# Peripherals.net
KiCad netlist of a schematic drawn in Altium Designer
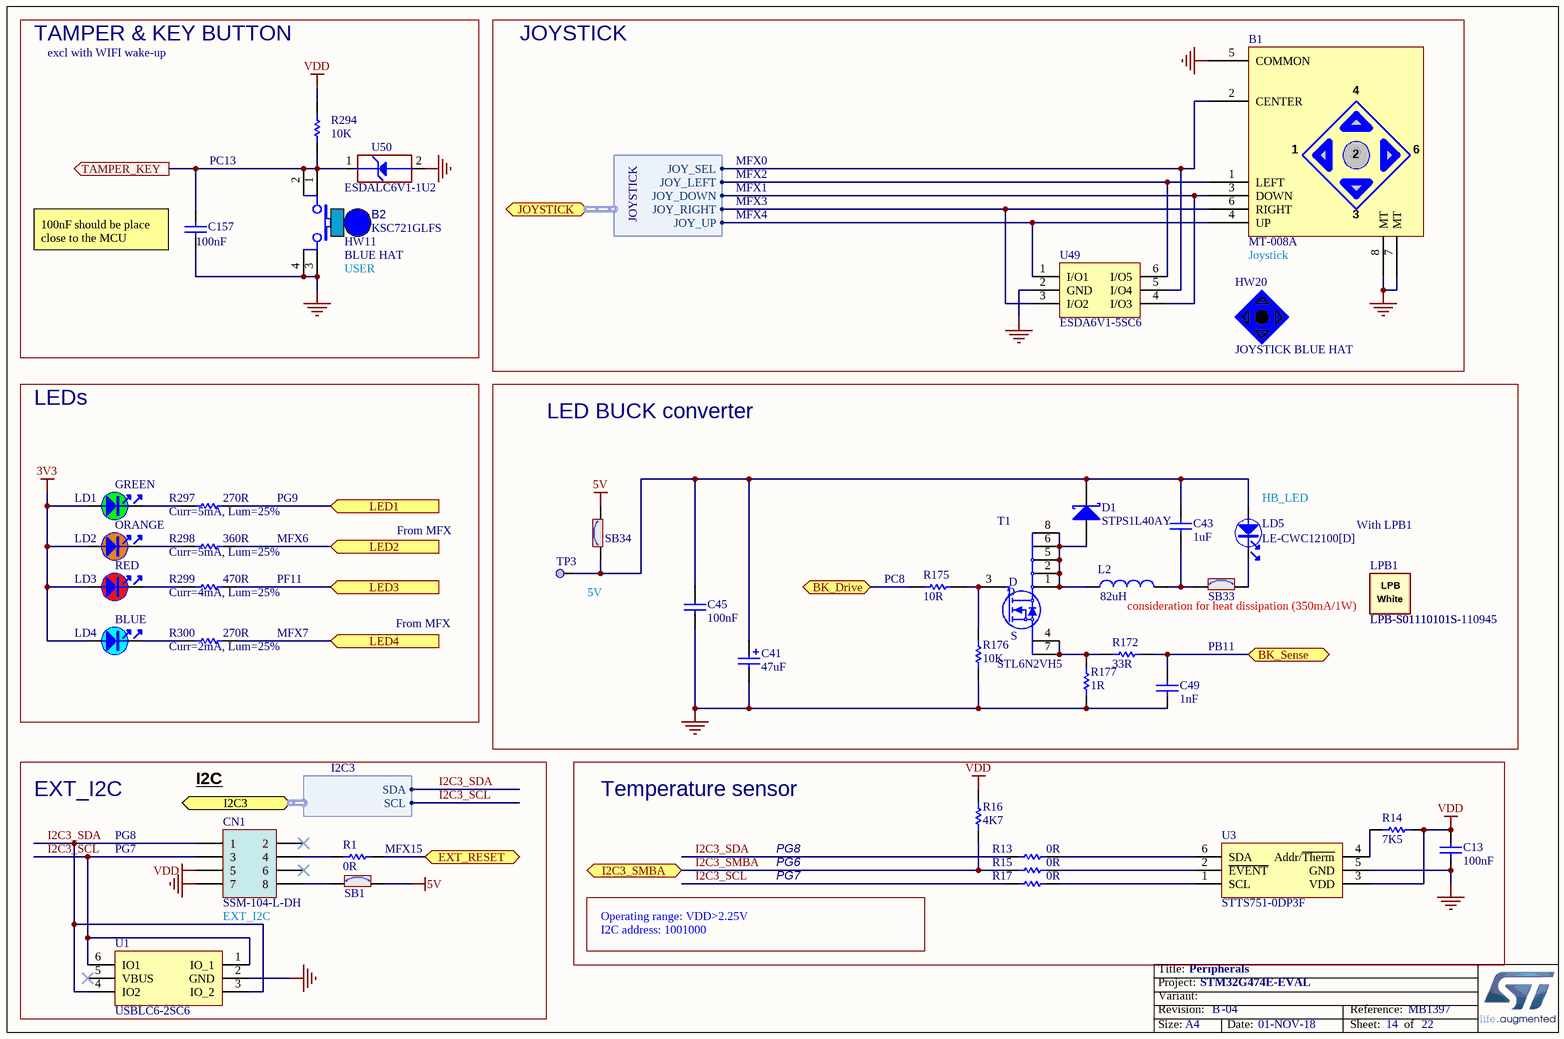
[diagram p0: Peripherals.SchDoc]

(export (version "E")
  (design (tool "Eeschema 10.0.6"))
  (components
    (comp (ref "B1")
      (value "MT-008A")
      (footprint "SWI_XIEJIA_MT-008A_6P")
      (description "Joystick, 4 dir, 1 OK")
      (fields
        (field (name "INTERNAL_PART_NUMBER") "MCD-00132")
        (field (name "MANUFACTURER") "XIEJIA Electronics")
        (field (name "PROVIDED_BY") "SUBCO")
      )
      (libsource (lib "MCD_PARTS_database") (part "Joystick MT-008A_M"))
    )
    (comp (ref "B2")
      (value "KSC721GLFS")
      (footprint "SWI_C&K_KSC721GLFS_BLUE")
      (description "Switch HW BLUE High4.3mm 2.25 Newtons")
      (fields
        (field (name "INTERNAL_PART_NUMBER") "MCD-00176")
        (field (name "MANUFACTURER") "C&K")
        (field (name "PROVIDED_BY") "SUBCO")
      )
      (libsource (lib "MCD_PARTS_database") (part "SW_BLUE_KSC721GLFS"))
    )
    (comp (ref "C13")
      (value "100nF")
      (footprint "C0603")
      (description "Capacitor, MLCC, 100nF, 16V, X7R, 10%, 0603, T=0,8mm")
      (fields
        (field (name "INTERNAL_PART_NUMBER") "MCD-00211")
        (field (name "MANUFACTURER_PART_NUMBER") "CC0603KRX7R7BB104")
        (field (name "PROVIDED_BY") "SUBCO")
      )
      (libsource (lib "MCD_PARTS_database") (part "Capacitor"))
    )
    (comp (ref "C41")
      (value "47uF")
      (footprint "CPOL_TAJ-C_2312_H2P6")
      (description "Capacitor, Tantalum, 47uF, 16V, 10%, TypeC")
      (fields
        (field (name "INTERNAL_PART_NUMBER") "MCD-00559")
        (field (name "MANUFACTURER_PART_NUMBER") "TAJC476K016RNJ")
        (field (name "PROVIDED_BY") "SUBCO")
      )
      (libsource (lib "MCD_PARTS_database") (part "Cap_POL_TANA"))
    )
    (comp (ref "C43")
      (value "1uF")
      (footprint "C0603")
      (description "Capacitor, MLCC, 1uF, 16V, X5R, 10%, 0603, T=0,8mm")
      (fields
        (field (name "INTERNAL_PART_NUMBER") "MCD-00010")
        (field (name "MANUFACTURER_PART_NUMBER") "CC0603KRX5R7BB105")
        (field (name "PROVIDED_BY") "SUBCO")
      )
      (libsource (lib "MCD_PARTS_database") (part "Capacitor"))
    )
    (comp (ref "C45")
      (value "100nF")
      (footprint "C0603")
      (description "Capacitor, MLCC, 100nF, 16V, X7R, 10%, 0603, T=0,8mm")
      (fields
        (field (name "INTERNAL_PART_NUMBER") "MCD-00211")
        (field (name "MANUFACTURER_PART_NUMBER") "CC0603KRX7R7BB104")
        (field (name "PROVIDED_BY") "SUBCO")
      )
      (libsource (lib "MCD_PARTS_database") (part "Capacitor"))
    )
    (comp (ref "C49")
      (value "1nF")
      (footprint "C0402")
      (description "Capacitor, MLCC, 1nF, 16V, X7R, 10%, 0402, T=0.5mm")
      (fields
        (field (name "INTERNAL_PART_NUMBER") "MCD-00198")
        (field (name "MANUFACTURER_PART_NUMBER") "CC0402KRX7R7BB102")
        (field (name "PROVIDED_BY") "SUBCO")
      )
      (libsource (lib "MCD_PARTS_database") (part "Capacitor"))
    )
    (comp (ref "C157")
      (value "100nF")
      (footprint "C0402")
      (description "Capacitor, MLCC, 100nF, 16V, X7R, 10%, 0402, T=0.5mm")
      (fields
        (field (name "INTERNAL_PART_NUMBER") "MCD-00006")
        (field (name "MANUFACTURER_PART_NUMBER") "CC0402KRX7R7BB104")
        (field (name "PROVIDED_BY") "SUBCO")
      )
      (libsource (lib "MCD_PARTS_database") (part "Capacitor"))
    )
    (comp (ref "CN1")
      (value "SSM-104-L-DH")
      (footprint "CON_SAMTEC_SSM-104-L-DH")
      (description "Socket, 4x2, 2.54mm, RA, SMT, Height 5.72mm")
      (fields
        (field (name "INTERNAL_PART_NUMBER") "MCD-00131")
        (field (name "MANUFACTURER") "SAMTEC")
        (field (name "PROVIDED_BY") "SUBCO")
      )
      (libsource (lib "MCD_PARTS_database") (part "Socket 4x2"))
    )
    (comp (ref "D1")
      (value "STPS1L40AY")
      (footprint "DIO_SMA_1A_2K")
      (description "Low Drop power Schottky rectifier(1A, 40V, 0.37 V)")
      (fields
        (field (name "INTERNAL_PART_NUMBER") "MCD-00606")
        (field (name "MANUFACTURER") "STMICROELECTRONICS")
        (field (name "PROVIDED_BY") "SUBCO with ST control")
      )
      (libsource (lib "MCD_PARTS_database") (part "SCHOTTKY"))
    )
    (comp (ref "HW11")
      (value "BLUE HAT")
      (description "Blue Hat for switch TD0341X-G01-BLU")
      (fields
        (field (name "INTERNAL_PART_NUMBER") "MCD-00634")
        (field (name "MANUFACTURER_PART_NUMBER") "988.16.09.3.00002_SH-517")
        (field (name "PROVIDED_BY") "SUBCO")
      )
      (libsource (lib "MCD_PARTS_database") (part "BUTTON_HAT_BLUE"))
    )
    (comp (ref "HW20")
      (value "JOYSTICK BLUE HAT")
      (description "Joystick BLue Hat")
      (fields
        (field (name "INTERNAL_PART_NUMBER") "MCD-01337")
        (field (name "MANUFACTURER_PART_NUMBER") "KTSC-62-B")
        (field (name "PROVIDED_BY") "SUBCO")
      )
      (libsource (lib "MCD_PARTS_database") (part "JOYSTICK_BLUE_HAT"))
    )
    (comp (ref "L2")
      (value "82uH")
      (footprint "IND_POWER_CYNTEC_PSI054T")
      (description "SMD power inductor. 82uH, 1.0A, 400mohm, 4.9x4.9x4.0mm")
      (fields
        (field (name "INTERNAL_PART_NUMBER") "MCD-01190")
        (field (name "MANUFACTURER_PART_NUMBER") "PSI054T-820MS-11")
        (field (name "PROVIDED_BY") "SUBCO")
      )
      (libsource (lib "MCD_PARTS_database") (part "Inductor"))
    )
    (comp (ref "LD1")
      (value "GREEN")
      (footprint "LED_0603_OSRAM_LG-Q396-PS-35_GREEN_1A2K_H0P4")
      (description "LED Green, 0603 SMD, Forward Voltage Typ=2V, Max=2.5V")
      (fields
        (field (name "INTERNAL_PART_NUMBER") "MCD-00588")
        (field (name "MANUFACTURER_PART_NUMBER") "LG Q396-PS-35")
        (field (name "PROVIDED_BY") "SUBCO")
      )
      (libsource (lib "MCD_PARTS_database") (part "LED_green"))
    )
    (comp (ref "LD2")
      (value "ORANGE")
      (footprint "LED_0603_OSRAM_LO-Q976-PS-25_ORANGE_1A2K_H0P8")
      (description "LED Orange, 0603 SMD, Forward Voltage Min=1.6V, Max=2.4V")
      (fields
        (field (name "INTERNAL_PART_NUMBER") "MCD-00590")
        (field (name "MANUFACTURER_PART_NUMBER") "LO Q976-PS-25")
        (field (name "PROVIDED_BY") "SUBCO")
      )
      (libsource (lib "MCD_PARTS_database") (part "LED_orange"))
    )
    (comp (ref "LD3")
      (value "RED")
      (footprint "LED_0603_VISHAY_VLMS1300-GS08_RED_1A2K_H0P8")
      (description "LED Red, 0603 SMD, 2V Forward Voltage")
      (fields
        (field (name "INTERNAL_PART_NUMBER") "MCD-00587")
        (field (name "MANUFACTURER_PART_NUMBER") "VLMS1300-GS08")
        (field (name "PROVIDED_BY") "SUBCO")
      )
      (libsource (lib "MCD_PARTS_database") (part "LED_red"))
    )
    (comp (ref "LD4")
      (value "BLUE")
      (footprint "LED_0603_OSRAM_LB-Q39G-L2OO-35-1_BLUE_1A2K_H0P4")
      (description "LED Blue, 0603 SMD, Forward Voltage Min=2,8V, Max=3,8V")
      (fields
        (field (name "INTERNAL_PART_NUMBER") "MCD-00585")
        (field (name "MANUFACTURER_PART_NUMBER") "LB Q39G-L2OO-35-1")
        (field (name "PROVIDED_BY") "SUBCO")
      )
      (libsource (lib "MCD_PARTS_database") (part "LED_blue"))
    )
    (comp (ref "LD5")
      (value "LE-CWC12100[D]")
      (footprint "LED_EVERLUCK_CWC12100_WHITE_1A2K")
      (description "White SMD LED lamp, Forward Voltage Typ=2.8V, Max=3.6V")
      (fields
        (field (name "INTERNAL_PART_NUMBER") "MCD-01186")
        (field (name "MANUFACTURER") "EVERLUCK")
        (field (name "PROVIDED_BY") "SUBCO")
      )
      (libsource (lib "MCD_PARTS_database") (part "LED_white"))
    )
    (comp (ref "LPB1")
      (value "LPB-S01110101S")
      (footprint "LIGHT_10MM-SQUARE-LIGHT-BAR_LUMEX_LPB-S01110101S-110945")
      (description "10mm Square Light Bar.")
      (fields
        (field (name "INTERNAL_PART_NUMBER") "MCD-01191")
        (field (name "ALTIUM_VALUE") "LPB-S01110101S-110945")
        (field (name "MANUFACTURER_PART_NUMBER") "LPB-S01110101S-110945")
        (field (name "PROVIDED_BY") "SUBCO")
      )
      (libsource (lib "MCD_PARTS_database") (part "LPB-S01110101S"))
    )
    (comp (ref "R1")
      (value "0R")
      (footprint "R0402")
      (description "Resistor,0R,0402,5%,1/16W")
      (fields
        (field (name "INTERNAL_PART_NUMBER") "MCD-00052")
        (field (name "MANUFACTURER_PART_NUMBER") "RC0402JR-070RL")
        (field (name "PROVIDED_BY") "SUBCO")
      )
      (libsource (lib "MCD_PARTS_database") (part "Resistor"))
    )
    (comp (ref "R13")
      (value "0R")
      (footprint "R0603")
      (description "Resistor,0R,0603,5%,1/10W")
      (fields
        (field (name "INTERNAL_PART_NUMBER") "MCD-00056")
        (field (name "MANUFACTURER_PART_NUMBER") "RC0603JR-070RL")
        (field (name "PROVIDED_BY") "SUBCO")
      )
      (libsource (lib "MCD_PARTS_database") (part "Resistor"))
    )
    (comp (ref "R14")
      (value "7K5")
      (footprint "R0603")
      (description "Resistor,7K5,0603,1%,1/10W")
      (fields
        (field (name "INTERNAL_PART_NUMBER") "MCD-00520")
        (field (name "MANUFACTURER_PART_NUMBER") "RC0603FR-077K5L")
        (field (name "PROVIDED_BY") "SUBCO")
      )
      (libsource (lib "MCD_PARTS_database") (part "Resistor"))
    )
    (comp (ref "R15")
      (value "0R")
      (footprint "R0603")
      (description "Resistor,0R,0603,5%,1/10W")
      (fields
        (field (name "INTERNAL_PART_NUMBER") "MCD-00056")
        (field (name "MANUFACTURER_PART_NUMBER") "RC0603JR-070RL")
        (field (name "PROVIDED_BY") "SUBCO")
      )
      (libsource (lib "MCD_PARTS_database") (part "Resistor"))
    )
    (comp (ref "R16")
      (value "4K7")
      (footprint "R0402")
      (description "Resistor,4K7,0402,1%,1/16W")
      (fields
        (field (name "INTERNAL_PART_NUMBER") "MCD-00065")
        (field (name "MANUFACTURER_PART_NUMBER") "RC0402FR-074K7L")
        (field (name "PROVIDED_BY") "SUBCO")
      )
      (libsource (lib "MCD_PARTS_database") (part "Resistor"))
    )
    (comp (ref "R17")
      (value "0R")
      (footprint "R0603")
      (description "Resistor,0R,0603,5%,1/10W")
      (fields
        (field (name "INTERNAL_PART_NUMBER") "MCD-00056")
        (field (name "MANUFACTURER_PART_NUMBER") "RC0603JR-070RL")
        (field (name "PROVIDED_BY") "SUBCO")
      )
      (libsource (lib "MCD_PARTS_database") (part "Resistor"))
    )
    (comp (ref "R172")
      (value "33R")
      (footprint "R0603")
      (description "Resistor,33R,0603,1%,1/10W")
      (fields
        (field (name "INTERNAL_PART_NUMBER") "MCD-00456")
        (field (name "MANUFACTURER_PART_NUMBER") "RC0603FR-0733RL")
        (field (name "PROVIDED_BY") "SUBCO")
      )
      (libsource (lib "MCD_PARTS_database") (part "Resistor"))
    )
    (comp (ref "R175")
      (value "10R")
      (footprint "R0805")
      (description "Resistor,10R,0805,1%,Stackpole,1/4W")
      (fields
        (field (name "INTERNAL_PART_NUMBER") "MCD-01111")
        (field (name "MANUFACTURER_PART_NUMBER") "RNCP0805FTD10R0")
        (field (name "PROVIDED_BY") "SUBCO")
      )
      (libsource (lib "MCD_PARTS_database") (part "Resistor"))
    )
    (comp (ref "R176")
      (value "10K")
      (footprint "R0603")
      (description "Resistor,10K,0603,1%,1/10W")
      (fields
        (field (name "INTERNAL_PART_NUMBER") "MCD-00220")
        (field (name "MANUFACTURER_PART_NUMBER") "RC0603FR-0710KL")
        (field (name "PROVIDED_BY") "SUBCO")
      )
      (libsource (lib "MCD_PARTS_database") (part "Resistor"))
    )
    (comp (ref "R177")
      (value "1R")
      (footprint "R1206_H0P55")
      (description "Resistor, 1R, 1206, 1%, 1/4W")
      (fields
        (field (name "INTERNAL_PART_NUMBER") "MCD-01185")
        (field (name "MANUFACTURER_PART_NUMBER") "CRCW12061R00FKEA")
        (field (name "PROVIDED_BY") "SUBCO")
      )
      (libsource (lib "MCD_PARTS_database") (part "Resistor"))
    )
    (comp (ref "R294")
      (value "10K")
      (footprint "R0402")
      (description "Resistor,10K,0402,1%,1/16W")
      (fields
        (field (name "INTERNAL_PART_NUMBER") "MCD-00053")
        (field (name "MANUFACTURER_PART_NUMBER") "RC0402FR-0710KL")
        (field (name "PROVIDED_BY") "SUBCO")
      )
      (libsource (lib "MCD_PARTS_database") (part "Resistor"))
    )
    (comp (ref "R297")
      (value "270R")
      (footprint "R0603")
      (description "Resistor,270R,0603,1%,1/10W")
      (fields
        (field (name "INTERNAL_PART_NUMBER") "MCD-00442")
        (field (name "MANUFACTURER_PART_NUMBER") "RC0603FR-07270RL")
        (field (name "PROVIDED_BY") "SUBCO")
      )
      (libsource (lib "MCD_PARTS_database") (part "Resistor"))
    )
    (comp (ref "R298")
      (value "360R")
      (footprint "R0603")
      (description "Resistor,360R,0603,1%,1/10W")
      (fields
        (field (name "INTERNAL_PART_NUMBER") "MCD-00462")
        (field (name "MANUFACTURER_PART_NUMBER") "RC0603FR-07360RL")
        (field (name "PROVIDED_BY") "SUBCO")
      )
      (libsource (lib "MCD_PARTS_database") (part "Resistor"))
    )
    (comp (ref "R299")
      (value "470R")
      (footprint "R0603")
      (description "Resistor,470R,0603,1%,1/10W")
      (fields
        (field (name "INTERNAL_PART_NUMBER") "MCD-00354")
        (field (name "MANUFACTURER_PART_NUMBER") "RC0603FR-07470RL")
        (field (name "PROVIDED_BY") "SUBCO")
      )
      (libsource (lib "MCD_PARTS_database") (part "Resistor"))
    )
    (comp (ref "R300")
      (value "270R")
      (footprint "R0603")
      (description "Resistor,270R,0603,1%,1/10W")
      (fields
        (field (name "INTERNAL_PART_NUMBER") "MCD-00442")
        (field (name "MANUFACTURER_PART_NUMBER") "RC0603FR-07270RL")
        (field (name "PROVIDED_BY") "SUBCO")
      )
      (libsource (lib "MCD_PARTS_database") (part "Resistor"))
    )
    (comp (ref "SB1")
      (value "SB_ON")
      (footprint "SOLDER-BRIDGE_R0603-0R")
      (description "Solder Bridge ON")
      (fields
        (field (name "INTERNAL_PART_NUMBER") "MCD-00071")
        (field (name "MANUFACTURER_PART_NUMBER") "RC0603JR-070RL")
        (field (name "PROVIDED_BY") "SUBCO")
      )
      (libsource (lib "MCD_PARTS_database") (part "SB_ON"))
    )
    (comp (ref "SB33")
      (value "SB_ON")
      (footprint "SOLDER-BRIDGE_R0603-0R")
      (description "Solder Bridge ON")
      (fields
        (field (name "INTERNAL_PART_NUMBER") "MCD-00071")
        (field (name "MANUFACTURER_PART_NUMBER") "RC0603JR-070RL")
        (field (name "PROVIDED_BY") "SUBCO")
      )
      (libsource (lib "MCD_PARTS_database") (part "SB_ON"))
    )
    (comp (ref "SB34")
      (value "SB_ON")
      (footprint "SOLDER-BRIDGE_R0603-0R")
      (description "Solder Bridge ON")
      (fields
        (field (name "INTERNAL_PART_NUMBER") "MCD-00071")
        (field (name "MANUFACTURER_PART_NUMBER") "RC0603JR-070RL")
        (field (name "PROVIDED_BY") "SUBCO")
      )
      (libsource (lib "") (part "SB_ON_1"))
    )
    (comp (ref "T1")
      (value "STL6N2VH5")
      (footprint "MOS_POWERFLAT_2X2_P065")
      (description "N-channel 20 V, 0.025 O typ., 6 A STripFET™ V Power MOSFET in a PowerFLAT™ 2x2 package")
      (fields
        (field (name "INTERNAL_PART_NUMBER") "MCD-01028")
        (field (name "MANUFACTURER") "STMICROELECTRONICS")
        (field (name "PROVIDED_BY") "SUBCO with ST control")
      )
      (libsource (lib "MCD_PARTS_database") (part "STL6N2VH5"))
    )
    (comp (ref "TP3")
      (value "Test Point")
      (footprint "TP_SMD_1MM")
      (description "Test Point 1mm")
      (fields (field (name "INTERNAL_PART_NUMBER") "MCD-00074") (field (name "MANUFACTURER") "n/a"))
      (libsource (lib "MCD_PARTS_database") (part "Test Point"))
    )
    (comp (ref "U1")
      (value "USBLC6-2SC6")
      (footprint "ESD_SOT23-6L")
      (description "Very low capacitance ESD protection")
      (fields
        (field (name "INTERNAL_PART_NUMBER") "MCD-00163")
        (field (name "MANUFACTURER") "STMICROELECTRONICS")
        (field (name "PROVIDED_BY") "SUBCO with ST control")
      )
      (libsource (lib "MCD_PARTS_database") (part "USBLC6-2SC6"))
    )
    (comp (ref "U3")
      (value "STTS751-0DP3F")
      (footprint "ICC_UDFN6_2X2_P065")
      (description "IC, 2.25 V low-voltage local digital temperature sensor, UDFN-6L")
      (fields
        (field (name "INTERNAL_PART_NUMBER") "MCD-01551")
        (field (name "MANUFACTURER") "STMICROELECTRONICS")
        (field (name "PROVIDED_BY") "SUBCO with ST control")
      )
      (libsource (lib "MCD_PARTS_database") (part "STTS751-0DP3F"))
    )
    (comp (ref "U49")
      (value "ESDA6V1-5SC6")
      (footprint "ESD_SOT23-6L")
      (description "5 unidirectional Transil diodes ESD protection")
      (fields
        (field (name "INTERNAL_PART_NUMBER") "MCD-01066")
        (field (name "MANUFACTURER") "STMICROELECTRONICS")
        (field (name "PROVIDED_BY") "SUBCO with ST control")
      )
      (libsource (lib "MCD_PARTS_database") (part "ESDA6V1-5SC6"))
    )
    (comp (ref "U50")
      (value "ESDALC6V1-1U2")
      (footprint "ESD_ST0201")
      (description "ESD protection 6V1")
      (fields
        (field (name "INTERNAL_PART_NUMBER") "MCD-00170")
        (field (name "MANUFACTURER") "STMICROELECTRONICS")
        (field (name "PROVIDED_BY") "SUBCO with ST control")
      )
      (libsource (lib "MCD_PARTS_database") (part "ESD-TRANSIL"))
    )
  )
  (nets
    (net (code "3") (name "/BK_Drive") (class "Default")
      (node (ref "R175") (pin "1") (pinfunction "1_1") (pintype "passive"))
    )
    (net (code "4") (name "/BK_Sense") (class "Default")
      (node (ref "C49") (pin "2") (pinfunction "2_2") (pintype "passive"))
      (node (ref "R172") (pin "2") (pinfunction "2_2") (pintype "passive"))
    )
    (net (code "5") (name "/EXT_RESET") (class "Default")
      (node (ref "R1") (pin "2") (pinfunction "2_2") (pintype "passive"))
    )
    (net (code "6") (name "/I2C3_SCL") (class "Default")
      (node (ref "CN1") (pin "3") (pinfunction "3_3") (pintype "passive"))
      (node (ref "R17") (pin "1") (pinfunction "1_1") (pintype "passive"))
      (node (ref "U1") (pin "1") (pinfunction "IO_1_1") (pintype "passive"))
      (node (ref "U1") (pin "6") (pinfunction "IO1_6") (pintype "passive"))
    )
    (net (code "7") (name "/I2C3_SDA") (class "Default")
      (node (ref "CN1") (pin "1") (pinfunction "1_1") (pintype "passive"))
      (node (ref "R13") (pin "1") (pinfunction "1_1") (pintype "passive"))
      (node (ref "U1") (pin "3") (pinfunction "IO_2_3") (pintype "passive"))
      (node (ref "U1") (pin "4") (pinfunction "IO2_4") (pintype "passive"))
    )
    (net (code "8") (name "/I2C3_SMBA") (class "Default")
      (node (ref "R15") (pin "1") (pinfunction "1_1") (pintype "passive"))
      (node (ref "R16") (pin "1") (pinfunction "1_1") (pintype "passive"))
    )
    (net (code "9") (name "/LED1") (class "Default")
      (node (ref "R297") (pin "2") (pinfunction "2_2") (pintype "passive"))
    )
    (net (code "10") (name "/LED2") (class "Default")
      (node (ref "R298") (pin "2") (pinfunction "2_2") (pintype "passive"))
    )
    (net (code "11") (name "/LED3") (class "Default")
      (node (ref "R299") (pin "2") (pinfunction "2_2") (pintype "passive"))
    )
    (net (code "12") (name "/LED4") (class "Default")
      (node (ref "R300") (pin "2") (pinfunction "2_2") (pintype "passive"))
    )
    (net (code "13") (name "/TAMPER_KEY") (class "Default")
      (node (ref "B2") (pin "1") (pinfunction "1_1") (pintype "passive"))
      (node (ref "B2") (pin "2") (pinfunction "2_2") (pintype "passive"))
      (node (ref "C157") (pin "2") (pinfunction "2_2") (pintype "passive"))
      (node (ref "R294") (pin "1") (pinfunction "1_1") (pintype "passive"))
      (node (ref "U50") (pin "1") (pinfunction "IO1_1") (pintype "passive"))
    )
    (net (code "16") (name "3V3") (class "Default")
      (node (ref "LD1") (pin "1") (pintype "passive"))
      (node (ref "LD2") (pin "1") (pintype "passive"))
      (node (ref "LD3") (pin "1") (pintype "passive"))
      (node (ref "LD4") (pin "1") (pintype "passive"))
    )
    (net (code "17") (name "5V") (class "Default")
      (node (ref "SB1") (pin "2") (pinfunction "2_2") (pintype "passive"))
      (node (ref "SB34") (pin "2") (pinfunction "2_2") (pintype "passive"))
    )
    (net (code "18") (name "GND") (class "Default")
      (node (ref "B1") (pin "5") (pinfunction "COMMON_5") (pintype "passive"))
      (node (ref "B1") (pin "7") (pinfunction "MT_7") (pintype "passive"))
      (node (ref "B1") (pin "8") (pinfunction "MT_8") (pintype "passive"))
      (node (ref "B2") (pin "3") (pinfunction "3_3") (pintype "passive"))
      (node (ref "B2") (pin "4") (pinfunction "4_4") (pintype "passive"))
      (node (ref "C13") (pin "2") (pinfunction "2_2") (pintype "passive"))
      (node (ref "C157") (pin "1") (pinfunction "1_1") (pintype "passive"))
      (node (ref "C41") (pin "2") (pinfunction "2_2") (pintype "passive"))
      (node (ref "C45") (pin "1") (pinfunction "1_1") (pintype "passive"))
      (node (ref "C49") (pin "1") (pinfunction "1_1") (pintype "passive"))
      (node (ref "CN1") (pin "7") (pinfunction "7_7") (pintype "passive"))
      (node (ref "R176") (pin "1") (pinfunction "1_1") (pintype "passive"))
      (node (ref "R177") (pin "1") (pinfunction "1_1") (pintype "passive"))
      (node (ref "U1") (pin "2") (pinfunction "GND_2") (pintype "passive"))
      (node (ref "U3") (pin "5") (pinfunction "GND_5") (pintype "passive"))
      (node (ref "U49") (pin "2") (pinfunction "GND_2") (pintype "passive"))
      (node (ref "U50") (pin "2") (pinfunction "GND_2") (pintype "passive"))
    )
    (net (code "19") (name "Net-(B1-CENTER)") (class "Default")
      (node (ref "B1") (pin "2") (pinfunction "CENTER_2") (pintype "passive"))
      (node (ref "U49") (pin "5") (pinfunction "I/O4_5") (pintype "passive"))
    )
    (net (code "20") (name "Net-(B1-DOWN)") (class "Default")
      (node (ref "B1") (pin "3") (pinfunction "DOWN_3") (pintype "passive"))
      (node (ref "U49") (pin "4") (pinfunction "I/O3_4") (pintype "passive"))
    )
    (net (code "21") (name "Net-(B1-LEFT)") (class "Default")
      (node (ref "B1") (pin "1") (pinfunction "LEFT_1") (pintype "passive"))
      (node (ref "U49") (pin "6") (pinfunction "I/O5_6") (pintype "passive"))
    )
    (net (code "22") (name "Net-(B1-RIGHT)") (class "Default")
      (node (ref "B1") (pin "6") (pinfunction "RIGHT_6") (pintype "passive"))
      (node (ref "U49") (pin "3") (pinfunction "I/O2_3") (pintype "passive"))
    )
    (net (code "23") (name "Net-(B1-UP)") (class "Default")
      (node (ref "B1") (pin "4") (pinfunction "UP_4") (pintype "passive"))
      (node (ref "U49") (pin "1") (pinfunction "I/O1_1") (pintype "passive"))
    )
    (net (code "24") (name "Net-(C43-Pad1)") (class "Default")
      (node (ref "C43") (pin "1") (pinfunction "1_1") (pintype "passive"))
      (node (ref "L2") (pin "2") (pinfunction "2_2") (pintype "passive"))
      (node (ref "SB33") (pin "1") (pinfunction "1_1") (pintype "passive"))
    )
    (net (code "25") (name "Net-(CN1-Pad4)") (class "Default")
      (node (ref "CN1") (pin "4") (pinfunction "4_4") (pintype "passive"))
      (node (ref "R1") (pin "1") (pinfunction "1_1") (pintype "passive"))
    )
    (net (code "26") (name "Net-(CN1-Pad8)") (class "Default")
      (node (ref "CN1") (pin "8") (pinfunction "8_8") (pintype "passive"))
      (node (ref "SB1") (pin "1") (pinfunction "1_1") (pintype "passive"))
    )
    (net (code "27") (name "Net-(D1-A)") (class "Default")
      (node (ref "D1") (pin "1") (pinfunction "A_1") (pintype "passive"))
      (node (ref "L2") (pin "1") (pinfunction "1_1") (pintype "passive"))
      (node (ref "T1") (pin "1") (pinfunction "D_1") (pintype "passive"))
      (node (ref "T1") (pin "2") (pinfunction "D_2") (pintype "passive"))
      (node (ref "T1") (pin "5") (pinfunction "D_5") (pintype "passive"))
      (node (ref "T1") (pin "6") (pinfunction "D_6") (pintype "passive"))
      (node (ref "T1") (pin "8") (pinfunction "D_8") (pintype "passive"))
    )
    (net (code "28") (name "Net-(D1-K)") (class "Default")
      (node (ref "C41") (pin "1") (pinfunction "1_1") (pintype "passive"))
      (node (ref "C43") (pin "2") (pinfunction "2_2") (pintype "passive"))
      (node (ref "C45") (pin "2") (pinfunction "2_2") (pintype "passive"))
      (node (ref "D1") (pin "2") (pinfunction "K_2") (pintype "passive"))
      (node (ref "LD5") (pin "1") (pintype "passive"))
      (node (ref "SB34") (pin "1") (pinfunction "1_1") (pintype "passive"))
      (node (ref "TP3") (pin "1") (pinfunction "1_1") (pintype "passive"))
    )
    (net (code "29") (name "Net-(LD1-Pad2)") (class "Default")
      (node (ref "LD1") (pin "2") (pintype "passive"))
      (node (ref "R297") (pin "1") (pinfunction "1_1") (pintype "passive"))
    )
    (net (code "30") (name "Net-(LD2-Pad2)") (class "Default")
      (node (ref "LD2") (pin "2") (pintype "passive"))
      (node (ref "R298") (pin "1") (pinfunction "1_1") (pintype "passive"))
    )
    (net (code "31") (name "Net-(LD3-Pad2)") (class "Default")
      (node (ref "LD3") (pin "2") (pintype "passive"))
      (node (ref "R299") (pin "1") (pinfunction "1_1") (pintype "passive"))
    )
    (net (code "32") (name "Net-(LD4-Pad2)") (class "Default")
      (node (ref "LD4") (pin "2") (pintype "passive"))
      (node (ref "R300") (pin "1") (pinfunction "1_1") (pintype "passive"))
    )
    (net (code "33") (name "Net-(LD5-Pad2)") (class "Default")
      (node (ref "LD5") (pin "2") (pintype "passive"))
      (node (ref "SB33") (pin "2") (pinfunction "2_2") (pintype "passive"))
    )
    (net (code "34") (name "Net-(R172-Pad1)") (class "Default")
      (node (ref "R172") (pin "1") (pinfunction "1_1") (pintype "passive"))
      (node (ref "R177") (pin "2") (pinfunction "2_2") (pintype "passive"))
      (node (ref "T1") (pin "4") (pinfunction "S_4") (pintype "passive"))
      (node (ref "T1") (pin "7") (pinfunction "S_7") (pintype "passive"))
    )
    (net (code "35") (name "Net-(T1-G)") (class "Default")
      (node (ref "R175") (pin "2") (pinfunction "2_2") (pintype "passive"))
      (node (ref "R176") (pin "2") (pinfunction "2_2") (pintype "passive"))
      (node (ref "T1") (pin "3") (pinfunction "G_3") (pintype "passive"))
    )
    (net (code "36") (name "Net-(U3-Addr{slash}~{Therm})") (class "Default")
      (node (ref "R14") (pin "1") (pinfunction "1_1") (pintype "passive"))
      (node (ref "U3") (pin "4") (pinfunction "Addr/~{Therm}_4") (pintype "passive"))
    )
    (net (code "37") (name "Net-(U3-SCL)") (class "Default")
      (node (ref "R17") (pin "2") (pinfunction "2_2") (pintype "passive"))
      (node (ref "U3") (pin "1") (pinfunction "SCL_1") (pintype "passive"))
    )
    (net (code "38") (name "Net-(U3-SDA)") (class "Default")
      (node (ref "R13") (pin "2") (pinfunction "2_2") (pintype "passive"))
      (node (ref "U3") (pin "6") (pinfunction "SDA_6") (pintype "passive"))
    )
    (net (code "39") (name "Net-(U3-~{EVENT})") (class "Default")
      (node (ref "R15") (pin "2") (pinfunction "2_2") (pintype "passive"))
      (node (ref "U3") (pin "2") (pinfunction "~{EVENT}_2") (pintype "passive"))
    )
    (net (code "40") (name "VDD") (class "Default")
      (node (ref "C13") (pin "1") (pinfunction "1_1") (pintype "passive"))
      (node (ref "CN1") (pin "5") (pinfunction "5_5") (pintype "passive"))
      (node (ref "R14") (pin "2") (pinfunction "2_2") (pintype "passive"))
      (node (ref "R16") (pin "2") (pinfunction "2_2") (pintype "passive"))
      (node (ref "R294") (pin "2") (pinfunction "2_2") (pintype "passive"))
      (node (ref "U3") (pin "3") (pinfunction "VDD_3") (pintype "passive"))
    )
    (net (code "41") (name "unconnected-(CN1-Pad2)") (class "Default")
      (node (ref "CN1") (pin "2") (pinfunction "2_2") (pintype "passive+no_connect"))
    )
    (net (code "42") (name "unconnected-(CN1-Pad6)") (class "Default")
      (node (ref "CN1") (pin "6") (pinfunction "6_6") (pintype "passive+no_connect"))
    )
    (net (code "43") (name "unconnected-(U1-VBUS-Pad5)") (class "Default")
      (node (ref "U1") (pin "5") (pinfunction "VBUS_5") (pintype "passive+no_connect"))
    )
  )
)
